# Main.net
KiCad netlist of a schematic drawn in Altium Designer
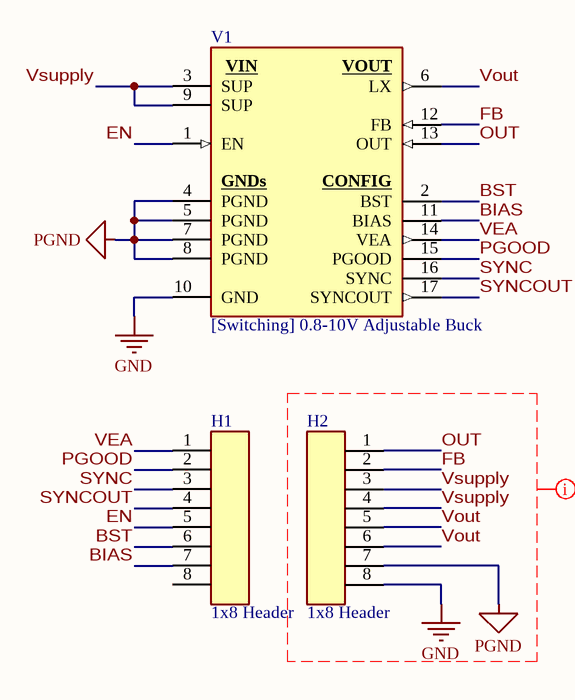
[diagram p0: Main.SchDoc]

(export (version "E")
  (design (tool "Eeschema 10.0.6"))
  (components
    (comp (ref "H1")
      (value "1x8 Header")
      (footprint "[Header] 1x8 Male")
      (description "2.54mm pitch")
      (libsource (lib "") (part "[Header] 1x8 Male_1"))
    )
    (comp (ref "H2")
      (value "1x8 Header")
      (footprint "[Header] 1x8 Male")
      (description "2.54mm pitch")
      (libsource (lib "Connectors") (part "[Header] 1x8 Male"))
    )
    (comp (ref "V1")
      (value "[Switching] 0.8-10V Adjustable Buck")
      (footprint "[Switching] 0.8-10V Adjustable Buck")
      (description "MAX20408AFOF/VY+")
      (libsource (lib "Voltage Regulators") (part "[Switching] 0.8-10V Adjustable Buck"))
    )
  )
  (nets
    (net (code "1") (name "/BIAS") (class "Default")
      (node (ref "H1") (pin "7") (pinfunction "7_7") (pintype "passive"))
      (node (ref "V1") (pin "11") (pinfunction "BIAS_11") (pintype "power_in"))
    )
    (net (code "2") (name "/BST") (class "Default")
      (node (ref "H1") (pin "6") (pinfunction "6_6") (pintype "passive"))
      (node (ref "V1") (pin "2") (pinfunction "BST_2") (pintype "power_in"))
    )
    (net (code "3") (name "/EN") (class "Default")
      (node (ref "H1") (pin "5") (pinfunction "5_5") (pintype "passive"))
      (node (ref "V1") (pin "1") (pinfunction "EN_1") (pintype "input"))
    )
    (net (code "4") (name "/FB") (class "Default")
      (node (ref "H2") (pin "2") (pinfunction "2_2") (pintype "passive"))
      (node (ref "V1") (pin "12") (pinfunction "FB_12") (pintype "input"))
    )
    (net (code "5") (name "/OUT") (class "Default")
      (node (ref "H2") (pin "1") (pinfunction "1_1") (pintype "passive"))
      (node (ref "V1") (pin "13") (pinfunction "OUT_13") (pintype "input"))
    )
    (net (code "6") (name "/PGOOD") (class "Default")
      (node (ref "H1") (pin "2") (pinfunction "2_2") (pintype "passive"))
      (node (ref "V1") (pin "15") (pinfunction "PGOOD_15") (pintype "open_collector"))
    )
    (net (code "7") (name "/SYNC") (class "Default")
      (node (ref "H1") (pin "3") (pinfunction "3_3") (pintype "passive"))
      (node (ref "V1") (pin "16") (pinfunction "SYNC_16") (pintype "passive"))
    )
    (net (code "8") (name "/SYNCOUT") (class "Default")
      (node (ref "H1") (pin "4") (pinfunction "4_4") (pintype "passive"))
      (node (ref "V1") (pin "17") (pinfunction "SYNCOUT_17") (pintype "output"))
    )
    (net (code "9") (name "/VEA") (class "Default")
      (node (ref "H1") (pin "1") (pinfunction "1_1") (pintype "passive"))
      (node (ref "V1") (pin "14") (pinfunction "VEA_14") (pintype "output"))
    )
    (net (code "10") (name "/Vout") (class "Default")
      (node (ref "H2") (pin "5") (pinfunction "5_5") (pintype "passive"))
      (node (ref "H2") (pin "6") (pinfunction "6_6") (pintype "passive"))
      (node (ref "V1") (pin "6") (pinfunction "LX_6") (pintype "output"))
    )
    (net (code "11") (name "/Vsupply") (class "Default")
      (node (ref "H2") (pin "3") (pinfunction "3_3") (pintype "passive"))
      (node (ref "H2") (pin "4") (pinfunction "4_4") (pintype "passive"))
      (node (ref "V1") (pin "3") (pinfunction "SUP_3") (pintype "power_in"))
      (node (ref "V1") (pin "9") (pinfunction "SUP_9") (pintype "power_in"))
    )
    (net (code "12") (name "GND") (class "Default")
      (node (ref "H2") (pin "8") (pinfunction "8_8") (pintype "passive"))
      (node (ref "V1") (pin "10") (pinfunction "GND_10") (pintype "power_in"))
    )
    (net (code "13") (name "PGND") (class "Default")
      (node (ref "H2") (pin "7") (pinfunction "7_7") (pintype "passive"))
      (node (ref "V1") (pin "4") (pinfunction "PGND_4") (pintype "power_in"))
      (node (ref "V1") (pin "5") (pinfunction "PGND_5") (pintype "power_in"))
      (node (ref "V1") (pin "7") (pinfunction "PGND_7") (pintype "power_in"))
      (node (ref "V1") (pin "8") (pinfunction "PGND_8") (pintype "power_in"))
    )
    (net (code "14") (name "unconnected-(H1-Pad8)") (class "Default")
      (node (ref "H1") (pin "8") (pinfunction "8_8") (pintype "passive"))
    )
  )
)
